# PCIe_USB30_Conn_Panel_Top.net
KiCad netlist of a schematic drawn in Altium Designer
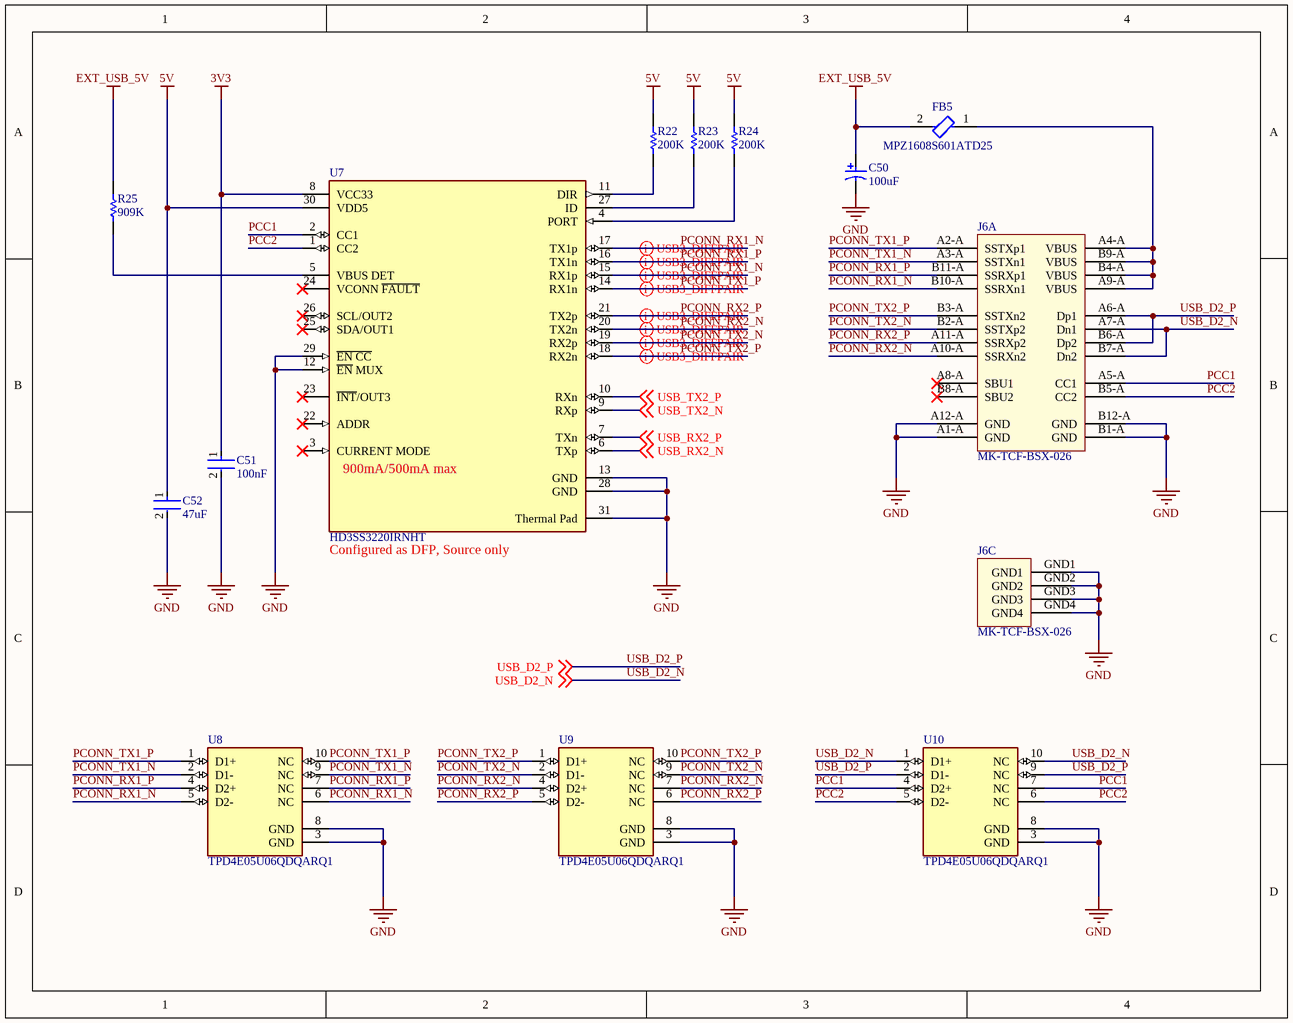
[diagram p0: PCIe_USB30_Conn_Panel_Top.SchDoc]

(export (version "E")
  (design (tool "Eeschema 10.0.6"))
  (components
    (comp (ref "C50")
      (value "100uF")
      (footprint "PNSC-EEEFK1C101P_L")
      (fields (field (name "MANUFACTURER") "Panasonic"))
      (libsource (lib "Altium Content Vault") (part "CAP-P-2"))
    )
    (comp (ref "C51")
      (value "100nF")
      (footprint "FP-C0402-BB-MFG")
      (description "CAP CER 0.1UF 10V X5R 0402")
      (fields (field (name "MANUFACTURER") "Kemet") (field (name "TOLERANCE") "0.1"))
      (libsource (lib "Altium Content Vault") (part "b4654b650e69147ec39a6b967a45e02"))
    )
    (comp (ref "C52")
      (value "47uF")
      (footprint "FP-C2012-125-0_2-IPC_B")
      (description "Multilayer Ceramic Capacitors 47μF ±20% 10V X5R SMD 0805")
      (fields (field (name "VOLTAGE") "10V") (field (name "TOLERANCE") "20%"))
      (libsource (lib "Altium Content Vault") (part "b4654b650e69147ec39a6b967a45e02"))
    )
    (comp (ref "FB5")
      (value "MPZ1608S601ATD25")
      (footprint "FP-MPZ1608-0_8-IPC_B")
      (description "Power line Ferrite Bead 600Ω @ 100MHz 1A DCR 0.15Ω AEC-Q200 SMD 0603")
      (fields (field (name "TOLERANCE") "25%"))
      (libsource (lib "Altium Content Vault") (part "5f30dd21d616792df468990f7003faa"))
    )
    (comp (ref "J6")
      (value "MK-TCF-BSX-026")
      (footprint "MK-TCF-BSX-026")
      (libsource (lib "MK-TCF-BSX-026") (part "MK-TCF-BSX-026"))
    )
    (comp (ref "R22")
      (value "200K")
      (footprint "RESC1005X40X25NL05T05")
      (description "Chip Resistor, 200 KOhm, +/- 1%, 100 mW, -55 to 155 degC, 0402 (1005 Metric), RoHS, Tape and Reel")
      (fields (field (name "PARTNUMBER") "ERJ-2RKF2003X") (field (name "TOLERANCE") "1%"))
      (libsource (lib "Altium Content Vault") (part "RES-2"))
    )
    (comp (ref "R23")
      (value "200K")
      (footprint "RESC1005X40X25NL05T05")
      (description "Chip Resistor, 200 KOhm, +/- 1%, 100 mW, -55 to 155 degC, 0402 (1005 Metric), RoHS, Tape and Reel")
      (fields (field (name "PARTNUMBER") "ERJ-2RKF2003X") (field (name "TOLERANCE") "1%"))
      (libsource (lib "Altium Content Vault") (part "RES-2"))
    )
    (comp (ref "R24")
      (value "200K")
      (footprint "RESC1005X40X25NL05T05")
      (description "Chip Resistor, 200 KOhm, +/- 1%, 100 mW, -55 to 155 degC, 0402 (1005 Metric), RoHS, Tape and Reel")
      (fields (field (name "PARTNUMBER") "ERJ-2RKF2003X") (field (name "TOLERANCE") "1%"))
      (libsource (lib "Altium Content Vault") (part "RES-2"))
    )
    (comp (ref "R25")
      (value "909K")
      (footprint "RESC1005X40X25NL05T10")
      (fields (field (name "MANUFACTURER") "Yageo / Phycomp") (field (name "PART NUMBER") "RC0402FR-07909KL"))
      (libsource (lib "Altium Content Vault") (part "RES"))
    )
    (comp (ref "U7")
      (value "HD3SS3220IRNHT")
      (footprint "FP-RNH0030A-MFG")
      (description "USB TYPE-C DRP PORT CONTROLLER W")
      (libsource (lib "Altium Content Vault") (part "bc1798bad1e85e1bff1291d9d73152b"))
    )
    (comp (ref "U8")
      (value "TPD4E05U06QDQARQ1")
      (footprint "FP-DQA0010A-MFG")
      (description "TVS DIODE 5.5V 14V 10USON")
      (fields
        (field (name "OCTOPART") "https://octopart.com/tpd4e05u06qdqarq1-texas+instruments-48523459")
        (field (name "MANUFACTURER") "Texas Instruments")
      )
      (libsource (lib "Altium Content Vault") (part "f11f7ff102fa2b028e1355c732c836d"))
    )
    (comp (ref "U9")
      (value "TPD4E05U06QDQARQ1")
      (footprint "FP-DQA0010A-MFG")
      (description "TVS DIODE 5.5V 14V 10USON")
      (fields
        (field (name "OCTOPART") "https://octopart.com/tpd4e05u06qdqarq1-texas+instruments-48523459")
        (field (name "MANUFACTURER") "Texas Instruments")
      )
      (libsource (lib "Altium Content Vault") (part "f11f7ff102fa2b028e1355c732c836d"))
    )
    (comp (ref "U10")
      (value "TPD4E05U06QDQARQ1")
      (footprint "FP-DQA0010A-MFG")
      (description "TVS DIODE 5.5V 14V 10USON")
      (fields
        (field (name "OCTOPART") "https://octopart.com/tpd4e05u06qdqarq1-texas+instruments-48523459")
        (field (name "MANUFACTURER") "Texas Instruments")
      )
      (libsource (lib "Altium Content Vault") (part "f11f7ff102fa2b028e1355c732c836d"))
    )
  )
  (nets
    (net (code "1") (name "/PCC1") (class "Default")
      (node (ref "J6") (pin "A5-A") (pinfunction "CC1_A5-A") (pintype "passive"))
      (node (ref "U10") (pin "4") (pinfunction "D2+_4") (pintype "bidirectional"))
      (node (ref "U10") (pin "7") (pinfunction "NC_7") (pintype "passive"))
      (node (ref "U7") (pin "2") (pinfunction "CC1_2") (pintype "bidirectional"))
    )
    (net (code "2") (name "/PCC2") (class "Default")
      (node (ref "J6") (pin "B5-A") (pinfunction "CC2_B5-A") (pintype "passive"))
      (node (ref "U10") (pin "5") (pinfunction "D2-_5") (pintype "bidirectional"))
      (node (ref "U10") (pin "6") (pinfunction "NC_6") (pintype "passive"))
      (node (ref "U7") (pin "1") (pinfunction "CC2_1") (pintype "bidirectional"))
    )
    (net (code "3") (name "/PCONN_RX1_N") (class "Default")
      (node (ref "J6") (pin "B10-A") (pinfunction "SSRXn1_B10-A") (pintype "passive"))
      (node (ref "U7") (pin "17") (pinfunction "TX1p_17") (pintype "bidirectional"))
      (node (ref "U8") (pin "5") (pinfunction "D2-_5") (pintype "bidirectional"))
      (node (ref "U8") (pin "6") (pinfunction "NC_6") (pintype "passive"))
    )
    (net (code "4") (name "/PCONN_RX1_P") (class "Default")
      (node (ref "J6") (pin "B11-A") (pinfunction "SSRXp1_B11-A") (pintype "passive"))
      (node (ref "U7") (pin "16") (pinfunction "TX1n_16") (pintype "bidirectional"))
      (node (ref "U8") (pin "4") (pinfunction "D2+_4") (pintype "bidirectional"))
      (node (ref "U8") (pin "7") (pinfunction "NC_7") (pintype "passive"))
    )
    (net (code "5") (name "/PCONN_RX2_N") (class "Default")
      (node (ref "J6") (pin "A10-A") (pinfunction "SSRXn2_A10-A") (pintype "passive"))
      (node (ref "U7") (pin "20") (pinfunction "TX2n_20") (pintype "bidirectional"))
      (node (ref "U9") (pin "4") (pinfunction "D2+_4") (pintype "bidirectional"))
      (node (ref "U9") (pin "7") (pinfunction "NC_7") (pintype "passive"))
    )
    (net (code "6") (name "/PCONN_RX2_P") (class "Default")
      (node (ref "J6") (pin "A11-A") (pinfunction "SSRXp2_A11-A") (pintype "passive"))
      (node (ref "U7") (pin "21") (pinfunction "TX2p_21") (pintype "bidirectional"))
      (node (ref "U9") (pin "5") (pinfunction "D2-_5") (pintype "bidirectional"))
      (node (ref "U9") (pin "6") (pinfunction "NC_6") (pintype "passive"))
    )
    (net (code "7") (name "/PCONN_TX1_N") (class "Default")
      (node (ref "J6") (pin "A3-A") (pinfunction "SSTXn1_A3-A") (pintype "passive"))
      (node (ref "U7") (pin "15") (pinfunction "RX1p_15") (pintype "bidirectional"))
      (node (ref "U8") (pin "2") (pinfunction "D1-_2") (pintype "bidirectional"))
      (node (ref "U8") (pin "9") (pinfunction "NC_9") (pintype "bidirectional"))
    )
    (net (code "8") (name "/PCONN_TX1_P") (class "Default")
      (node (ref "J6") (pin "A2-A") (pinfunction "SSTXp1_A2-A") (pintype "passive"))
      (node (ref "U7") (pin "14") (pinfunction "RX1n_14") (pintype "bidirectional"))
      (node (ref "U8") (pin "1") (pinfunction "D1+_1") (pintype "bidirectional"))
      (node (ref "U8") (pin "10") (pinfunction "NC_10") (pintype "bidirectional"))
    )
    (net (code "9") (name "/PCONN_TX2_N") (class "Default")
      (node (ref "J6") (pin "B2-A") (pinfunction "SSTXp2_B2-A") (pintype "passive"))
      (node (ref "U7") (pin "19") (pinfunction "RX2p_19") (pintype "bidirectional"))
      (node (ref "U9") (pin "2") (pinfunction "D1-_2") (pintype "bidirectional"))
      (node (ref "U9") (pin "9") (pinfunction "NC_9") (pintype "bidirectional"))
    )
    (net (code "10") (name "/PCONN_TX2_P") (class "Default")
      (node (ref "J6") (pin "B3-A") (pinfunction "SSTXn2_B3-A") (pintype "passive"))
      (node (ref "U7") (pin "18") (pinfunction "RX2n_18") (pintype "bidirectional"))
      (node (ref "U9") (pin "1") (pinfunction "D1+_1") (pintype "bidirectional"))
      (node (ref "U9") (pin "10") (pinfunction "NC_10") (pintype "bidirectional"))
    )
    (net (code "11") (name "3V3") (class "Default")
      (node (ref "C51") (pin "1") (pinfunction "1_1") (pintype "passive"))
      (node (ref "U7") (pin "8") (pinfunction "VCC33_8") (pintype "power_in"))
    )
    (net (code "12") (name "5V") (class "Default")
      (node (ref "C52") (pin "1") (pinfunction "1_1") (pintype "passive"))
      (node (ref "R22") (pin "2") (pinfunction "2_2") (pintype "passive"))
      (node (ref "R23") (pin "2") (pinfunction "2_2") (pintype "passive"))
      (node (ref "R24") (pin "2") (pinfunction "2_2") (pintype "passive"))
      (node (ref "U7") (pin "30") (pinfunction "VDD5_30") (pintype "power_in"))
    )
    (net (code "13") (name "EXT_USB_5V") (class "Default")
      (node (ref "C50") (pin "1") (pinfunction "1_1") (pintype "passive"))
      (node (ref "FB5") (pin "2") (pinfunction "2_2") (pintype "passive"))
      (node (ref "R25") (pin "2") (pinfunction "2_2") (pintype "passive"))
    )
    (net (code "14") (name "GND") (class "Default")
      (node (ref "C50") (pin "2") (pinfunction "2_2") (pintype "passive"))
      (node (ref "C51") (pin "2") (pinfunction "2_2") (pintype "passive"))
      (node (ref "C52") (pin "2") (pinfunction "2_2") (pintype "passive"))
      (node (ref "J6") (pin "A1-A") (pinfunction "GND_A1-A") (pintype "passive"))
      (node (ref "J6") (pin "A12-A") (pinfunction "GND_A12-A") (pintype "passive"))
      (node (ref "J6") (pin "B1-A") (pinfunction "GND_B1-A") (pintype "passive"))
      (node (ref "J6") (pin "B12-A") (pinfunction "GND_B12-A") (pintype "passive"))
      (node (ref "J6") (pin "GND1") (pinfunction "GND1_GND1") (pintype "passive"))
      (node (ref "J6") (pin "GND2") (pinfunction "GND2_GND2") (pintype "passive"))
      (node (ref "J6") (pin "GND3") (pinfunction "GND3_GND3") (pintype "passive"))
      (node (ref "J6") (pin "GND4") (pinfunction "GND4_GND4") (pintype "passive"))
      (node (ref "U10") (pin "3") (pinfunction "GND_3") (pintype "power_in"))
      (node (ref "U10") (pin "8") (pinfunction "GND_8") (pintype "power_in"))
      (node (ref "U7") (pin "12") (pinfunction "~{EN}_MUX_12") (pintype "input"))
      (node (ref "U7") (pin "13") (pinfunction "GND_13") (pintype "power_in"))
      (node (ref "U7") (pin "28") (pinfunction "GND_28") (pintype "power_in"))
      (node (ref "U7") (pin "29") (pinfunction "~{EN_CC}_29") (pintype "input"))
      (node (ref "U7") (pin "31") (pinfunction "Thermal_Pad_31") (pintype "power_in"))
      (node (ref "U8") (pin "3") (pinfunction "GND_3") (pintype "power_in"))
      (node (ref "U8") (pin "8") (pinfunction "GND_8") (pintype "power_in"))
      (node (ref "U9") (pin "3") (pinfunction "GND_3") (pintype "power_in"))
      (node (ref "U9") (pin "8") (pinfunction "GND_8") (pintype "power_in"))
    )
    (net (code "15") (name "Net-(FB5-Pad1)") (class "Default")
      (node (ref "FB5") (pin "1") (pinfunction "1_1") (pintype "passive"))
      (node (ref "J6") (pin "A4-A") (pinfunction "VBUS_A4-A") (pintype "passive"))
      (node (ref "J6") (pin "A9-A") (pinfunction "VBUS_A9-A") (pintype "passive"))
      (node (ref "J6") (pin "B4-A") (pinfunction "VBUS_B4-A") (pintype "passive"))
      (node (ref "J6") (pin "B9-A") (pinfunction "VBUS_B9-A") (pintype "passive"))
    )
    (net (code "16") (name "Net-(U7-DIR)") (class "Default")
      (node (ref "R22") (pin "1") (pinfunction "1_1") (pintype "passive"))
      (node (ref "U7") (pin "11") (pinfunction "DIR_11") (pintype "output"))
    )
    (net (code "17") (name "Net-(U7-ID)") (class "Default")
      (node (ref "R23") (pin "1") (pinfunction "1_1") (pintype "passive"))
      (node (ref "U7") (pin "27") (pinfunction "ID_27") (pintype "open_collector"))
    )
    (net (code "18") (name "Net-(U7-PORT)") (class "Default")
      (node (ref "R24") (pin "1") (pinfunction "1_1") (pintype "passive"))
      (node (ref "U7") (pin "4") (pinfunction "PORT_4") (pintype "input"))
    )
    (net (code "19") (name "Net-(U7-VBUS_DET)") (class "Default")
      (node (ref "R25") (pin "1") (pinfunction "1_1") (pintype "passive"))
      (node (ref "U7") (pin "5") (pinfunction "VBUS_DET_5") (pintype "power_in"))
    )
    (net (code "20") (name "USB_D2_N") (class "Default")
      (node (ref "J6") (pin "A7-A") (pinfunction "Dn1_A7-A") (pintype "passive"))
      (node (ref "J6") (pin "B7-A") (pinfunction "Dn2_B7-A") (pintype "passive"))
      (node (ref "U10") (pin "1") (pinfunction "D1+_1") (pintype "bidirectional"))
      (node (ref "U10") (pin "10") (pinfunction "NC_10") (pintype "bidirectional"))
    )
    (net (code "21") (name "USB_D2_P") (class "Default")
      (node (ref "J6") (pin "A6-A") (pinfunction "Dp1_A6-A") (pintype "passive"))
      (node (ref "J6") (pin "B6-A") (pinfunction "Dp2_B6-A") (pintype "passive"))
      (node (ref "U10") (pin "2") (pinfunction "D1-_2") (pintype "bidirectional"))
      (node (ref "U10") (pin "9") (pinfunction "NC_9") (pintype "bidirectional"))
    )
    (net (code "22") (name "USB_RX2_N") (class "Default")
      (node (ref "U7") (pin "6") (pinfunction "TXp_6") (pintype "bidirectional"))
    )
    (net (code "23") (name "USB_RX2_P") (class "Default")
      (node (ref "U7") (pin "7") (pinfunction "TXn_7") (pintype "bidirectional"))
    )
    (net (code "24") (name "USB_TX2_N") (class "Default")
      (node (ref "U7") (pin "9") (pinfunction "RXp_9") (pintype "bidirectional"))
    )
    (net (code "25") (name "USB_TX2_P") (class "Default")
      (node (ref "U7") (pin "10") (pinfunction "RXn_10") (pintype "bidirectional"))
    )
    (net (code "26") (name "unconnected-(J6A-SBU1-PadA8-A)") (class "Default")
      (node (ref "J6") (pin "A8-A") (pinfunction "SBU1_A8-A") (pintype "passive+no_connect"))
    )
    (net (code "27") (name "unconnected-(J6A-SBU2-PadB8-A)") (class "Default")
      (node (ref "J6") (pin "B8-A") (pinfunction "SBU2_B8-A") (pintype "passive+no_connect"))
    )
    (net (code "28") (name "unconnected-(U7-ADDR-Pad22)") (class "Default")
      (node (ref "U7") (pin "22") (pinfunction "ADDR_22") (pintype "input+no_connect"))
    )
    (net (code "29") (name "unconnected-(U7-CURRENT_MODE-Pad3)") (class "Default")
      (node (ref "U7") (pin "3") (pinfunction "CURRENT_MODE_3") (pintype "input+no_connect"))
    )
    (net (code "30") (name "unconnected-(U7-SCL{slash}OUT2-Pad26)") (class "Default")
      (node (ref "U7") (pin "26") (pinfunction "SCL/OUT2_26") (pintype "bidirectional+no_connect"))
    )
    (net (code "31") (name "unconnected-(U7-SDA{slash}OUT1-Pad25)") (class "Default")
      (node (ref "U7") (pin "25") (pinfunction "SDA/OUT1_25") (pintype "bidirectional+no_connect"))
    )
    (net (code "32") (name "unconnected-(U7-VCONN_~{FAULT}-Pad24)") (class "Default")
      (node (ref "U7") (pin "24") (pinfunction "VCONN_~{FAULT}_24") (pintype "open_collector+no_connect"))
    )
    (net (code "33") (name "unconnected-(U7-~{INT}{slash}OUT3-Pad23)") (class "Default")
      (node (ref "U7") (pin "23") (pinfunction "~{INT}/OUT3_23") (pintype "open_collector+no_connect"))
    )
  )
)
